# DVT-Atlas-Driver2.net
KiCad netlist of a schematic drawn in Altium Designer
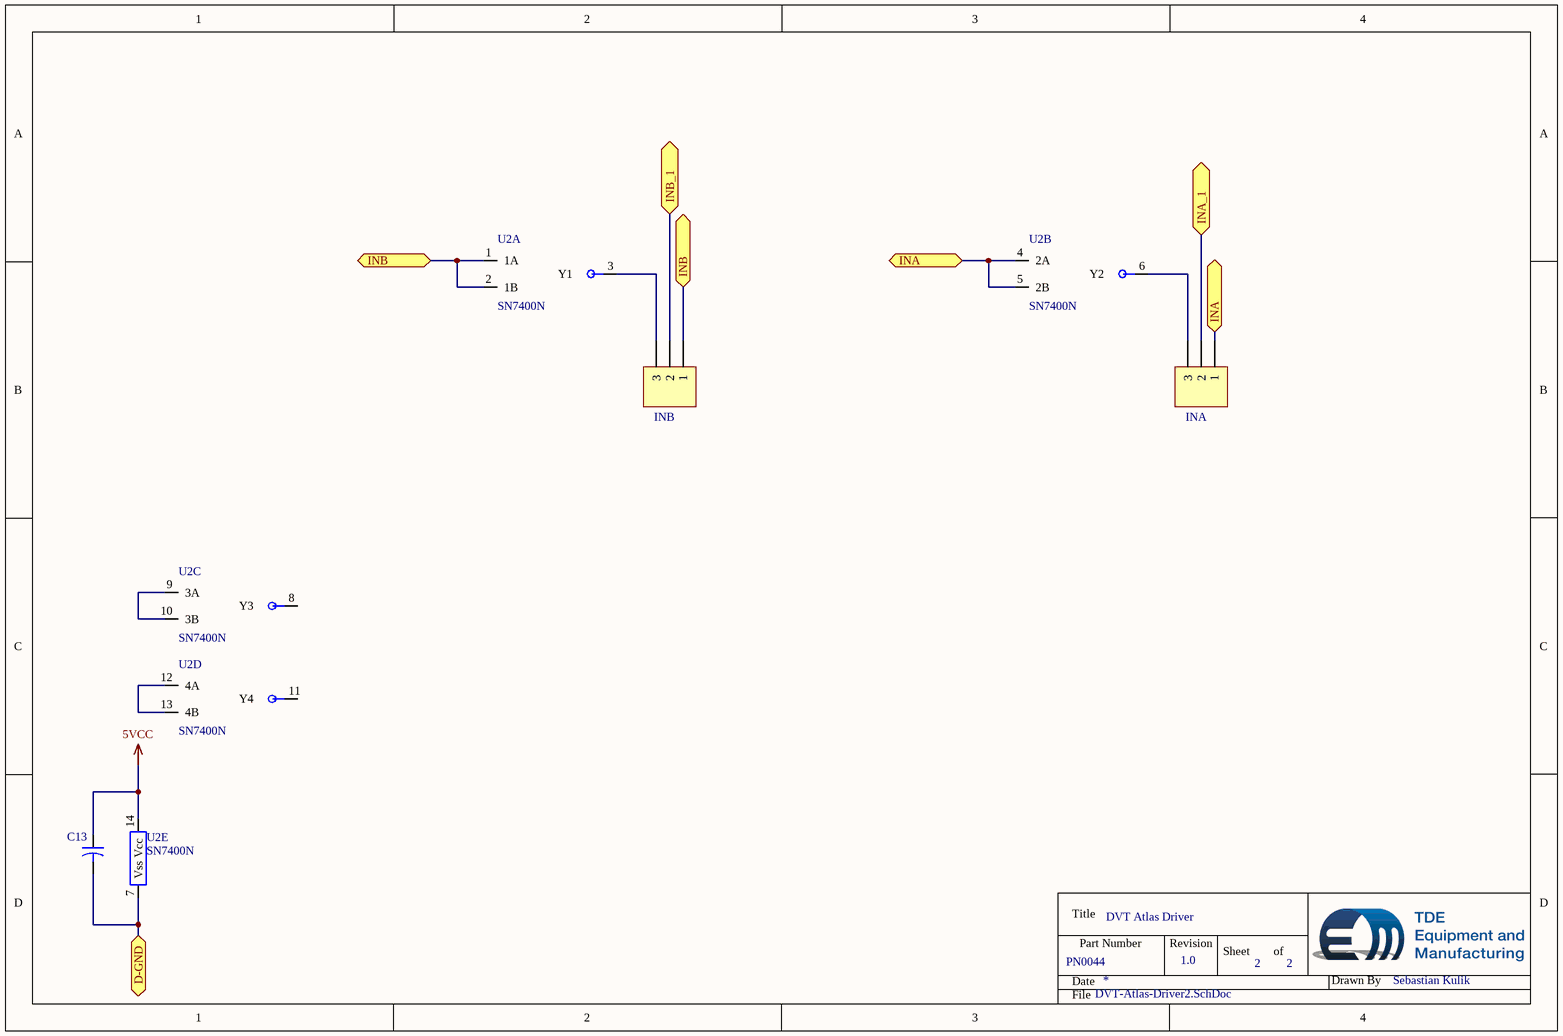
[diagram p0: DVT-Atlas-Driver2.SchDoc]

(export (version "E")
  (design (tool "Eeschema 10.0.6"))
  (components
    (comp (ref "C13")
      (value "Capacitor-Dummy-THT")
      (footprint "KEMET-C052H")
      (fields (field (name "PUBLISHER") "Sebastian Kulik"))
      (libsource (lib "Capacitors") (part "Capacitor-Dummy-THT"))
    )
    (comp (ref "INA")
      (value "Plug_3_90_2.54")
      (footprint "HDR1X3")
      (description "Plug,-3-Pin")
      (fields (field (name "MANUFACTURER") "WE") (field (name "PUBLISHER") "Sebastian Kulik"))
      (libsource (lib "Connectors") (part "Plug_3_90_2.54"))
    )
    (comp (ref "INB")
      (value "Plug_3_90_2.54")
      (footprint "HDR1X3")
      (description "Plug,-3-Pin")
      (fields (field (name "MANUFACTURER") "WE") (field (name "PUBLISHER") "Sebastian Kulik"))
      (libsource (lib "Connectors") (part "Plug_3_90_2.54"))
    )
    (comp (ref "U2")
      (value "SN7400N")
      (footprint "DIP-14")
      (description "Quad NAND, TTL")
      (fields (field (name "MANUFACTURER") "TI") (field (name "PUBLISHER") "Sebastian Kulik"))
      (libsource (lib "ICs") (part "SN7400N"))
    )
  )
  (nets
    (net (code "1") (name "/D-GND") (class "Default")
      (node (ref "C13") (pin "2") (pinfunction "2_2") (pintype "passive"))
      (node (ref "U2") (pin "7") (pinfunction "Vss_7") (pintype "passive"))
    )
    (net (code "2") (name "/INA") (class "Default")
      (node (ref "INA") (pin "1") (pinfunction "1_1") (pintype "passive"))
      (node (ref "U2") (pin "4") (pinfunction "2A_4") (pintype "passive"))
      (node (ref "U2") (pin "5") (pinfunction "2B_5") (pintype "passive"))
    )
    (net (code "3") (name "/INA_1") (class "Default")
      (node (ref "INA") (pin "2") (pinfunction "2_2") (pintype "passive"))
    )
    (net (code "4") (name "/INB") (class "Default")
      (node (ref "INB") (pin "1") (pinfunction "1_1") (pintype "passive"))
      (node (ref "U2") (pin "1") (pinfunction "1A_1") (pintype "passive"))
      (node (ref "U2") (pin "2") (pinfunction "1B_2") (pintype "passive"))
    )
    (net (code "5") (name "/INB_1") (class "Default")
      (node (ref "INB") (pin "2") (pinfunction "2_2") (pintype "passive"))
    )
    (net (code "6") (name "5VCC") (class "Default")
      (node (ref "C13") (pin "1") (pinfunction "1_1") (pintype "passive"))
      (node (ref "U2") (pin "14") (pinfunction "Vcc_14") (pintype "passive"))
    )
    (net (code "7") (name "Net-(U2A-Y1)") (class "Default")
      (node (ref "INB") (pin "3") (pinfunction "3_3") (pintype "passive"))
      (node (ref "U2") (pin "3") (pinfunction "Y1_3") (pintype "passive"))
    )
    (net (code "8") (name "Net-(U2B-Y2)") (class "Default")
      (node (ref "INA") (pin "3") (pinfunction "3_3") (pintype "passive"))
      (node (ref "U2") (pin "6") (pinfunction "Y2_6") (pintype "passive"))
    )
    (net (code "9") (name "Net-(U2C-3A)") (class "Default")
      (node (ref "U2") (pin "10") (pinfunction "3B_10") (pintype "passive"))
      (node (ref "U2") (pin "9") (pinfunction "3A_9") (pintype "passive"))
    )
    (net (code "10") (name "Net-(U2D-4A)") (class "Default")
      (node (ref "U2") (pin "12") (pinfunction "4A_12") (pintype "passive"))
      (node (ref "U2") (pin "13") (pinfunction "4B_13") (pintype "passive"))
    )
    (net (code "11") (name "unconnected-(U2C-Y3-Pad8)") (class "Default")
      (node (ref "U2") (pin "8") (pinfunction "Y3_8") (pintype "passive"))
    )
    (net (code "12") (name "unconnected-(U2D-Y4-Pad11)") (class "Default")
      (node (ref "U2") (pin "11") (pinfunction "Y4_11") (pintype "passive"))
    )
  )
)
